# Single_Channel_fNIRS.net
KiCad netlist of a schematic drawn in Altium Designer
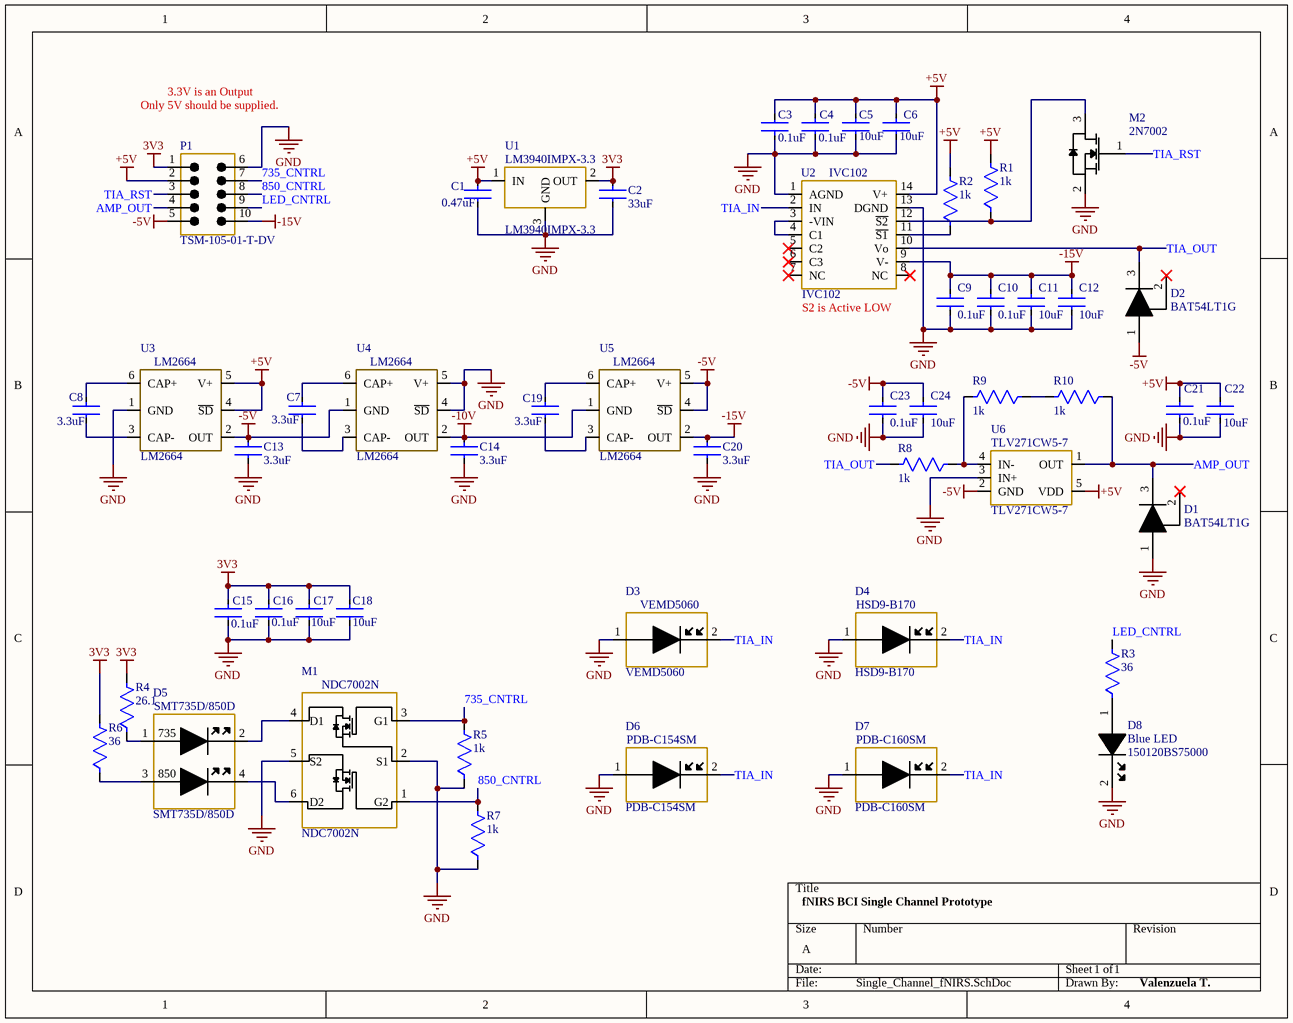
[diagram p0: Single_Channel_fNIRS.SchDoc]

(export (version "E")
  (design (tool "Eeschema 10.0.6"))
  (components
    (comp (ref "C1")
      (value "0.47uF")
      (footprint "CAPC3216X180N")
      (description "1206")
      (libsource (lib "Single_Channel_fNIRS") (part "C3216X7R2A474K160AA"))
    )
    (comp (ref "C2")
      (value "33uF")
      (footprint "CAPC3216X180N")
      (description "1206")
      (libsource (lib "Single_Channel_fNIRS") (part "C3216X5R1E336M160AC"))
    )
    (comp (ref "C3")
      (value "0.1uF")
      (footprint "CAPC3216X180N")
      (description "1206")
      (fields (field (name "TOLERANCE") "0.1") (field (name "MANUFACTURER") "KEMET"))
      (libsource (lib "Single_Channel_fNIRS") (part "C1206C104K5RAC7210"))
    )
    (comp (ref "C4")
      (value "0.1uF")
      (footprint "CAPC3216X180N")
      (description "1206")
      (fields (field (name "TOLERANCE") "0.1") (field (name "MANUFACTURER") "KEMET"))
      (libsource (lib "Single_Channel_fNIRS") (part "C1206C104K5RAC7210"))
    )
    (comp (ref "C5")
      (value "10uF")
      (footprint "CAPC3216X180N")
      (description "1206")
      (libsource (lib "Single_Channel_fNIRS") (part "CL31B106KOHNNWE"))
    )
    (comp (ref "C6")
      (value "10uF")
      (footprint "CAPC3216X180N")
      (description "1206")
      (libsource (lib "Single_Channel_fNIRS") (part "CL31B106KOHNNWE"))
    )
    (comp (ref "C7")
      (value "3.3uF")
      (footprint "CAPC1210(3225)190_M")
      (description "1210")
      (libsource (lib "Single_Channel_fNIRS") (part "C1210C335K5RAC7800"))
    )
    (comp (ref "C8")
      (value "3.3uF")
      (footprint "CAPC1210(3225)190_M")
      (description "1210")
      (libsource (lib "Single_Channel_fNIRS") (part "C1210C335K5RAC7800"))
    )
    (comp (ref "C9")
      (value "0.1uF")
      (footprint "CAPC3216X180N")
      (description "1206")
      (fields (field (name "TOLERANCE") "0.1") (field (name "MANUFACTURER") "KEMET"))
      (libsource (lib "Single_Channel_fNIRS") (part "C1206C104K5RAC7210"))
    )
    (comp (ref "C10")
      (value "0.1uF")
      (footprint "CAPC3216X180N")
      (description "1206")
      (fields (field (name "TOLERANCE") "0.1") (field (name "MANUFACTURER") "KEMET"))
      (libsource (lib "Single_Channel_fNIRS") (part "C1206C104K5RAC7210"))
    )
    (comp (ref "C11")
      (value "10uF")
      (footprint "CAPC3216X180N")
      (description "1206")
      (libsource (lib "Single_Channel_fNIRS") (part "CL31B106KOHNNWE"))
    )
    (comp (ref "C12")
      (value "10uF")
      (footprint "CAPC3216X180N")
      (description "1206")
      (libsource (lib "Single_Channel_fNIRS") (part "CL31B106KOHNNWE"))
    )
    (comp (ref "C13")
      (value "3.3uF")
      (footprint "CAPC1210(3225)190_M")
      (description "1210")
      (libsource (lib "Single_Channel_fNIRS") (part "C1210C335K5RAC7800"))
    )
    (comp (ref "C14")
      (value "3.3uF")
      (footprint "CAPC1210(3225)190_M")
      (description "1210")
      (libsource (lib "Single_Channel_fNIRS") (part "C1210C335K5RAC7800"))
    )
    (comp (ref "C15")
      (value "0.1uF")
      (footprint "CAPC3216X180N")
      (description "1206")
      (fields (field (name "TOLERANCE") "0.1") (field (name "MANUFACTURER") "KEMET"))
      (libsource (lib "Single_Channel_fNIRS") (part "C1206C104K5RAC7210"))
    )
    (comp (ref "C16")
      (value "0.1uF")
      (footprint "CAPC3216X180N")
      (description "1206")
      (fields (field (name "TOLERANCE") "0.1") (field (name "MANUFACTURER") "KEMET"))
      (libsource (lib "Single_Channel_fNIRS") (part "C1206C104K5RAC7210"))
    )
    (comp (ref "C17")
      (value "10uF")
      (footprint "CAPC3216X180N")
      (description "1206")
      (libsource (lib "Single_Channel_fNIRS") (part "CL31B106KOHNNWE"))
    )
    (comp (ref "C18")
      (value "10uF")
      (footprint "CAPC3216X180N")
      (description "1206")
      (libsource (lib "Single_Channel_fNIRS") (part "CL31B106KOHNNWE"))
    )
    (comp (ref "C19")
      (value "3.3uF")
      (footprint "CAPC1210(3225)190_M")
      (description "1210")
      (libsource (lib "Single_Channel_fNIRS") (part "C1210C335K5RAC7800"))
    )
    (comp (ref "C20")
      (value "3.3uF")
      (footprint "CAPC1210(3225)190_M")
      (description "1210")
      (libsource (lib "Single_Channel_fNIRS") (part "C1210C335K5RAC7800"))
    )
    (comp (ref "C21")
      (value "0.1uF")
      (footprint "CAPC3216X180N")
      (description "1206")
      (fields (field (name "TOLERANCE") "0.1") (field (name "MANUFACTURER") "KEMET"))
      (libsource (lib "Single_Channel_fNIRS") (part "C1206C104K5RAC7210"))
    )
    (comp (ref "C22")
      (value "10uF")
      (footprint "CAPC3216X180N")
      (description "1206")
      (libsource (lib "Single_Channel_fNIRS") (part "CL31B106KOHNNWE"))
    )
    (comp (ref "C23")
      (value "0.1uF")
      (footprint "CAPC3216X180N")
      (description "1206")
      (fields (field (name "TOLERANCE") "0.1") (field (name "MANUFACTURER") "KEMET"))
      (libsource (lib "Single_Channel_fNIRS") (part "C1206C104K5RAC7210"))
    )
    (comp (ref "C24")
      (value "10uF")
      (footprint "CAPC3216X180N")
      (description "1206")
      (libsource (lib "Single_Channel_fNIRS") (part "CL31B106KOHNNWE"))
    )
    (comp (ref "D1")
      (value "BAT54LT1G")
      (footprint "BAT54LT1")
      (description "Schottky Barrier Diode, 3-Pin SOT-23, Pb-Free, Tape and Reel")
      (fields (field (name "MANUFACTURER") "On Semiconductor"))
      (libsource (lib "Single_Channel_fNIRS") (part "BAT54L"))
    )
    (comp (ref "D2")
      (value "BAT54LT1G")
      (footprint "BAT54LT1")
      (description "Schottky Barrier Diode, 3-Pin SOT-23, Pb-Free, Tape and Reel")
      (fields (field (name "MANUFACTURER") "On Semiconductor"))
      (libsource (lib "Single_Channel_fNIRS") (part "BAT54L"))
    )
    (comp (ref "D3")
      (value "VEMD5060")
      (footprint "VEMD5060")
      (libsource (lib "Single_Channel_fNIRS") (part "VEMD5060"))
    )
    (comp (ref "D4")
      (value "HSD9-B170")
      (footprint "HSD9-B170")
      (libsource (lib "Single_Channel_fNIRS") (part "HSD9-B170"))
    )
    (comp (ref "D5")
      (value "SMT735D/850D")
      (footprint "SMT735D_850D")
      (libsource (lib "Single_Channel_fNIRS") (part "SMT735D/850D"))
    )
    (comp (ref "D6")
      (value "PDB-C154SM")
      (footprint "PDB-C154SM")
      (libsource (lib "Single_Channel_fNIRS") (part "PDB-C154SM"))
    )
    (comp (ref "D7")
      (value "PDB-C160SM")
      (footprint "DS-PDB-C160SM")
      (libsource (lib "Single_Channel_fNIRS") (part "PDB-C160SM"))
    )
    (comp (ref "D8")
      (value "Blue LED")
      (footprint "150120BS75000")
      (description "Single Color LED, Blue, Water Clear, 2mm")
      (fields
        (field (name "MANUFACTURER") "Wurth Electronics")
        (field (name "MANUFACTURER PART NUMBER") "150120BS75000")
        (field (name "SUPPLIER PART NUMBER 1") "150120BS75000")
      )
      (libsource (lib "Single_Channel_fNIRS") (part "150120BS75000"))
    )
    (comp (ref "M1")
      (value "NDC7002N")
      (footprint "FAIR-MA06A_V")
      (libsource (lib "Single_Channel_fNIRS") (part "NDC7002N"))
    )
    (comp (ref "M2")
      (value "2N7002")
      (footprint "STM-SOT-23-3_V")
      (description "N-channel 60 V, 1.8 Ohm, 0.35 A STripFET(TM) II Power MOSFET, SOT23")
      (fields (field (name "MANUFACTURER") "STMicroelectronics"))
      (libsource (lib "Single_Channel_fNIRS") (part "2N7002-TP"))
    )
    (comp (ref "P1")
      (value "TSM-105-01-T-DV")
      (footprint "SAMTEC_TSM-105-01-T-DV-TR")
      (fields (field (name "MANUFACTURER") "Samtec"))
      (libsource (lib "Single_Channel_fNIRS") (part "TSM-105-01-T-DV"))
    )
    (comp (ref "R1")
      (value "1k")
      (footprint "R1206")
      (description "1206 1kOhm")
      (libsource (lib "Single_Channel_fNIRS") (part "RT1206BRD071KL"))
    )
    (comp (ref "R2")
      (value "1k")
      (footprint "R1206")
      (description "1206 1kOhm")
      (libsource (lib "Single_Channel_fNIRS") (part "RT1206BRD071KL"))
    )
    (comp (ref "R3")
      (value "36")
      (footprint "R1206")
      (description "1206 36 Ohm")
      (fields
        (field (name "MANUFACTURER") "Yageo")
        (field (name "MANUFACTURER PART NUMBER") "RT1206BRD0736RL")
      )
      (libsource (lib "Single_Channel_fNIRS") (part "RT1206BRD0736RL"))
    )
    (comp (ref "R4")
      (value "26.1")
      (footprint "R1206")
      (description "1206 26.1 Ohm")
      (fields
        (field (name "OCTOPART") "https://octopart.com/rq73c2b26r1btd-te+connectivity-93911368")
        (field (name "MANUFACTURER PART NUMBER") "RQ73C2B26R1BTD")
      )
      (libsource (lib "Single_Channel_fNIRS") (part "RQ73C2B26R1BTD"))
    )
    (comp (ref "R5")
      (value "1k")
      (footprint "R1206")
      (description "1206 1kOhm")
      (libsource (lib "Single_Channel_fNIRS") (part "RT1206BRD071KL"))
    )
    (comp (ref "R6")
      (value "36")
      (footprint "R1206")
      (description "1206 36 Ohm")
      (fields
        (field (name "MANUFACTURER") "Yageo")
        (field (name "MANUFACTURER PART NUMBER") "RT1206BRD0736RL")
      )
      (libsource (lib "Single_Channel_fNIRS") (part "RT1206BRD0736RL"))
    )
    (comp (ref "R7")
      (value "1k")
      (footprint "R1206")
      (description "1206 1kOhm")
      (libsource (lib "Single_Channel_fNIRS") (part "RT1206BRD071KL"))
    )
    (comp (ref "R8")
      (value "1k")
      (footprint "R1206")
      (description "1206 1kOhm")
      (libsource (lib "Single_Channel_fNIRS") (part "RT1206BRD071KL"))
    )
    (comp (ref "R9")
      (value "1k")
      (footprint "R1206")
      (description "1206 1kOhm")
      (libsource (lib "Single_Channel_fNIRS") (part "RT1206BRD071KL"))
    )
    (comp (ref "R10")
      (value "1k")
      (footprint "R1206")
      (description "1206 1kOhm")
      (libsource (lib "Single_Channel_fNIRS") (part "RT1206BRD071KL"))
    )
    (comp (ref "U1")
      (value "LM3940IMPX-3.3")
      (footprint "LM3940")
      (libsource (lib "Single_Channel_fNIRS") (part "LM3940IMPX-3.3"))
    )
    (comp (ref "U2")
      (value "IVC102")
      (footprint "D0014A_M")
      (libsource (lib "Single_Channel_fNIRS") (part "IVC102"))
    )
    (comp (ref "U3")
      (value "LM2664")
      (footprint "LM2664")
      (description "Switched Capacitor Voltage Converter, 6-pin SOT-23")
      (fields (field (name "MANUFACTURER") "Texas Instruments"))
      (libsource (lib "Single_Channel_fNIRS") (part "LM2664"))
    )
    (comp (ref "U4")
      (value "LM2664")
      (footprint "LM2664")
      (description "Switched Capacitor Voltage Converter, 6-pin SOT-23")
      (fields (field (name "MANUFACTURER") "Texas Instruments"))
      (libsource (lib "Single_Channel_fNIRS") (part "LM2664"))
    )
    (comp (ref "U5")
      (value "LM2664")
      (footprint "LM2664")
      (description "Switched Capacitor Voltage Converter, 6-pin SOT-23")
      (fields (field (name "MANUFACTURER") "Texas Instruments"))
      (libsource (lib "Single_Channel_fNIRS") (part "LM2664"))
    )
    (comp (ref "U6")
      (value "TLV271CW5-7")
      (footprint "SOT95P285X145-5N")
      (libsource (lib "Single_Channel_fNIRS") (part "TLV271CW5-7"))
    )
  )
  (nets
    (net (code "1") (name "+5V") (class "Default")
      (node (ref "C1") (pin "1") (pinfunction "1_1") (pintype "passive"))
      (node (ref "C21") (pin "1") (pinfunction "1_1") (pintype "passive"))
      (node (ref "C22") (pin "1") (pinfunction "1_1") (pintype "passive"))
      (node (ref "C3") (pin "2") (pinfunction "2_2") (pintype "passive"))
      (node (ref "C4") (pin "1") (pinfunction "1_1") (pintype "passive"))
      (node (ref "C5") (pin "1") (pinfunction "1_1") (pintype "passive"))
      (node (ref "C6") (pin "1") (pinfunction "1_1") (pintype "passive"))
      (node (ref "P1") (pin "2") (pinfunction "2_2") (pintype "passive"))
      (node (ref "R1") (pin "2") (pinfunction "2_2") (pintype "passive"))
      (node (ref "R2") (pin "2") (pinfunction "2_2") (pintype "passive"))
      (node (ref "U1") (pin "1") (pinfunction "IN_1") (pintype "passive"))
      (node (ref "U2") (pin "14") (pinfunction "V+_14") (pintype "passive"))
      (node (ref "U3") (pin "4") (pinfunction "~{SD}_4") (pintype "passive"))
      (node (ref "U3") (pin "5") (pinfunction "V+_5") (pintype "passive"))
      (node (ref "U6") (pin "5") (pinfunction "VDD_5") (pintype "passive"))
    )
    (net (code "2") (name "-5V") (class "Default")
      (node (ref "C13") (pin "1") (pinfunction "1_1") (pintype "passive"))
      (node (ref "C23") (pin "1") (pinfunction "1_1") (pintype "passive"))
      (node (ref "C24") (pin "1") (pinfunction "1_1") (pintype "passive"))
      (node (ref "D2") (pin "1") (pinfunction "A_1") (pintype "passive"))
      (node (ref "P1") (pin "5") (pinfunction "5_5") (pintype "passive"))
      (node (ref "U3") (pin "2") (pinfunction "OUT_2") (pintype "passive"))
      (node (ref "U4") (pin "1") (pinfunction "GND_1") (pintype "passive"))
      (node (ref "U5") (pin "4") (pinfunction "~{SD}_4") (pintype "passive"))
      (node (ref "U5") (pin "5") (pinfunction "V+_5") (pintype "passive"))
      (node (ref "U6") (pin "2") (pinfunction "GND_2") (pintype "passive"))
    )
    (net (code "3") (name "-10V") (class "Default")
      (node (ref "C14") (pin "1") (pinfunction "1_1") (pintype "passive"))
      (node (ref "U4") (pin "2") (pinfunction "OUT_2") (pintype "passive"))
      (node (ref "U5") (pin "1") (pinfunction "GND_1") (pintype "passive"))
    )
    (net (code "4") (name "-15V") (class "Default")
      (node (ref "C10") (pin "1") (pinfunction "1_1") (pintype "passive"))
      (node (ref "C11") (pin "1") (pinfunction "1_1") (pintype "passive"))
      (node (ref "C12") (pin "1") (pinfunction "1_1") (pintype "passive"))
      (node (ref "C20") (pin "1") (pinfunction "1_1") (pintype "passive"))
      (node (ref "C9") (pin "1") (pinfunction "1_1") (pintype "passive"))
      (node (ref "P1") (pin "10") (pinfunction "10_10") (pintype "passive"))
      (node (ref "U2") (pin "9") (pinfunction "V-_9") (pintype "passive"))
      (node (ref "U5") (pin "2") (pinfunction "OUT_2") (pintype "passive"))
    )
    (net (code "5") (name "/735_CNTRL") (class "Default")
      (node (ref "M1") (pin "3") (pinfunction "G1_3") (pintype "passive"))
      (node (ref "P1") (pin "7") (pinfunction "7_7") (pintype "passive"))
      (node (ref "R5") (pin "2") (pinfunction "2_2") (pintype "passive"))
    )
    (net (code "6") (name "/850_CNTRL") (class "Default")
      (node (ref "M1") (pin "1") (pinfunction "G2_1") (pintype "passive"))
      (node (ref "P1") (pin "8") (pinfunction "8_8") (pintype "passive"))
      (node (ref "R7") (pin "2") (pinfunction "2_2") (pintype "passive"))
    )
    (net (code "7") (name "/AMP_OUT") (class "Default")
      (node (ref "D1") (pin "3") (pinfunction "K_3") (pintype "passive"))
      (node (ref "P1") (pin "4") (pinfunction "4_4") (pintype "passive"))
      (node (ref "R10") (pin "1") (pinfunction "1_1") (pintype "passive"))
      (node (ref "U6") (pin "1") (pinfunction "OUT_1") (pintype "passive"))
    )
    (net (code "8") (name "/LED_CNTRL") (class "Default")
      (node (ref "P1") (pin "9") (pinfunction "9_9") (pintype "passive"))
      (node (ref "R3") (pin "2") (pinfunction "2_2") (pintype "passive"))
    )
    (net (code "9") (name "/TIA_IN") (class "Default")
      (node (ref "D3") (pin "2") (pinfunction "2_2") (pintype "passive"))
      (node (ref "D4") (pin "2") (pinfunction "2_2") (pintype "passive"))
      (node (ref "D6") (pin "2") (pinfunction "2_2") (pintype "passive"))
      (node (ref "D7") (pin "2") (pinfunction "2_2") (pintype "passive"))
      (node (ref "U2") (pin "2") (pinfunction "IN_2") (pintype "passive"))
    )
    (net (code "10") (name "/TIA_OUT") (class "Default")
      (node (ref "D2") (pin "3") (pinfunction "K_3") (pintype "passive"))
      (node (ref "R8") (pin "2") (pinfunction "2_2") (pintype "passive"))
      (node (ref "U2") (pin "10") (pinfunction "Vo_10") (pintype "passive"))
    )
    (net (code "11") (name "/TIA_RST") (class "Default")
      (node (ref "M2") (pin "1") (pinfunction "G_1") (pintype "passive"))
      (node (ref "P1") (pin "3") (pinfunction "3_3") (pintype "passive"))
    )
    (net (code "12") (name "3V3") (class "Default")
      (node (ref "C15") (pin "1") (pinfunction "1_1") (pintype "passive"))
      (node (ref "C16") (pin "1") (pinfunction "1_1") (pintype "passive"))
      (node (ref "C17") (pin "1") (pinfunction "1_1") (pintype "passive"))
      (node (ref "C18") (pin "1") (pinfunction "1_1") (pintype "passive"))
      (node (ref "C2") (pin "1") (pinfunction "1_1") (pintype "passive"))
      (node (ref "P1") (pin "1") (pinfunction "1_1") (pintype "passive"))
      (node (ref "R4") (pin "2") (pinfunction "2_2") (pintype "passive"))
      (node (ref "R6") (pin "2") (pinfunction "2_2") (pintype "passive"))
      (node (ref "U1") (pin "2") (pinfunction "OUT_2") (pintype "passive"))
    )
    (net (code "13") (name "GND") (class "Default")
      (node (ref "C1") (pin "2") (pinfunction "2_2") (pintype "passive"))
      (node (ref "C10") (pin "2") (pinfunction "2_2") (pintype "passive"))
      (node (ref "C11") (pin "2") (pinfunction "2_2") (pintype "passive"))
      (node (ref "C12") (pin "2") (pinfunction "2_2") (pintype "passive"))
      (node (ref "C13") (pin "2") (pinfunction "2_2") (pintype "passive"))
      (node (ref "C14") (pin "2") (pinfunction "2_2") (pintype "passive"))
      (node (ref "C15") (pin "2") (pinfunction "2_2") (pintype "passive"))
      (node (ref "C16") (pin "2") (pinfunction "2_2") (pintype "passive"))
      (node (ref "C17") (pin "2") (pinfunction "2_2") (pintype "passive"))
      (node (ref "C18") (pin "2") (pinfunction "2_2") (pintype "passive"))
      (node (ref "C2") (pin "2") (pinfunction "2_2") (pintype "passive"))
      (node (ref "C20") (pin "2") (pinfunction "2_2") (pintype "passive"))
      (node (ref "C21") (pin "2") (pinfunction "2_2") (pintype "passive"))
      (node (ref "C22") (pin "2") (pinfunction "2_2") (pintype "passive"))
      (node (ref "C23") (pin "2") (pinfunction "2_2") (pintype "passive"))
      (node (ref "C24") (pin "2") (pinfunction "2_2") (pintype "passive"))
      (node (ref "C3") (pin "1") (pinfunction "1_1") (pintype "passive"))
      (node (ref "C4") (pin "2") (pinfunction "2_2") (pintype "passive"))
      (node (ref "C5") (pin "2") (pinfunction "2_2") (pintype "passive"))
      (node (ref "C6") (pin "2") (pinfunction "2_2") (pintype "passive"))
      (node (ref "C9") (pin "2") (pinfunction "2_2") (pintype "passive"))
      (node (ref "D1") (pin "1") (pinfunction "A_1") (pintype "passive"))
      (node (ref "D3") (pin "1") (pinfunction "1_1") (pintype "passive"))
      (node (ref "D4") (pin "1") (pinfunction "1_1") (pintype "passive"))
      (node (ref "D6") (pin "1") (pinfunction "1_1") (pintype "passive"))
      (node (ref "D7") (pin "1") (pinfunction "1_1") (pintype "passive"))
      (node (ref "D8") (pin "2") (pinfunction "2_2") (pintype "passive"))
      (node (ref "M1") (pin "2") (pinfunction "S1_2") (pintype "passive"))
      (node (ref "M1") (pin "5") (pinfunction "S2_5") (pintype "passive"))
      (node (ref "M2") (pin "2") (pinfunction "S_2") (pintype "passive"))
      (node (ref "P1") (pin "6") (pinfunction "6_6") (pintype "passive"))
      (node (ref "R5") (pin "1") (pinfunction "1_1") (pintype "passive"))
      (node (ref "R7") (pin "1") (pinfunction "1_1") (pintype "passive"))
      (node (ref "U1") (pin "3") (pinfunction "GND_3") (pintype "passive"))
      (node (ref "U2") (pin "1") (pinfunction "AGND_1") (pintype "passive"))
      (node (ref "U2") (pin "13") (pinfunction "DGND_13") (pintype "passive"))
      (node (ref "U3") (pin "1") (pinfunction "GND_1") (pintype "passive"))
      (node (ref "U4") (pin "4") (pinfunction "~{SD}_4") (pintype "passive"))
      (node (ref "U4") (pin "5") (pinfunction "V+_5") (pintype "passive"))
      (node (ref "U6") (pin "3") (pinfunction "IN+_3") (pintype "passive"))
    )
    (net (code "14") (name "Net-(D5-Pad1)") (class "Default")
      (node (ref "D5") (pin "1") (pinfunction "1_1") (pintype "passive"))
      (node (ref "R4") (pin "1") (pinfunction "1_1") (pintype "passive"))
    )
    (net (code "15") (name "Net-(D5-Pad3)") (class "Default")
      (node (ref "D5") (pin "3") (pinfunction "3_3") (pintype "passive"))
      (node (ref "R6") (pin "1") (pinfunction "1_1") (pintype "passive"))
    )
    (net (code "16") (name "Net-(D8-Pad1)") (class "Default")
      (node (ref "D8") (pin "1") (pinfunction "1_1") (pintype "passive"))
      (node (ref "R3") (pin "1") (pinfunction "1_1") (pintype "passive"))
    )
    (net (code "17") (name "Net-(M1-D1)") (class "Default")
      (node (ref "D5") (pin "2") (pinfunction "2_2") (pintype "passive"))
      (node (ref "M1") (pin "4") (pinfunction "D1_4") (pintype "passive"))
    )
    (net (code "18") (name "Net-(M1-D2)") (class "Default")
      (node (ref "D5") (pin "4") (pinfunction "4_4") (pintype "passive"))
      (node (ref "M1") (pin "6") (pinfunction "D2_6") (pintype "passive"))
    )
    (net (code "19") (name "Net-(M2-D)") (class "Default")
      (node (ref "M2") (pin "3") (pinfunction "D_3") (pintype "passive"))
      (node (ref "R1") (pin "1") (pinfunction "1_1") (pintype "passive"))
      (node (ref "U2") (pin "12") (pinfunction "~{S2}_12") (pintype "passive"))
    )
    (net (code "20") (name "Net-(R10-Pad2)") (class "Default")
      (node (ref "R10") (pin "2") (pinfunction "2_2") (pintype "passive"))
      (node (ref "R9") (pin "1") (pinfunction "1_1") (pintype "passive"))
    )
    (net (code "21") (name "Net-(U2--VIN)") (class "Default")
      (node (ref "U2") (pin "3") (pinfunction "-VIN_3") (pintype "passive"))
      (node (ref "U2") (pin "4") (pinfunction "C1_4") (pintype "passive"))
    )
    (net (code "22") (name "Net-(U2-~{S1})") (class "Default")
      (node (ref "R2") (pin "1") (pinfunction "1_1") (pintype "passive"))
      (node (ref "U2") (pin "11") (pinfunction "~{S1}_11") (pintype "passive"))
    )
    (net (code "23") (name "Net-(U3-CAP+)") (class "Default")
      (node (ref "C8") (pin "1") (pinfunction "1_1") (pintype "passive"))
      (node (ref "U3") (pin "6") (pinfunction "CAP+_6") (pintype "passive"))
    )
    (net (code "24") (name "Net-(U3-CAP-)") (class "Default")
      (node (ref "C8") (pin "2") (pinfunction "2_2") (pintype "passive"))
      (node (ref "U3") (pin "3") (pinfunction "CAP-_3") (pintype "passive"))
    )
    (net (code "25") (name "Net-(U4-CAP+)") (class "Default")
      (node (ref "C7") (pin "1") (pinfunction "1_1") (pintype "passive"))
      (node (ref "U4") (pin "6") (pinfunction "CAP+_6") (pintype "passive"))
    )
    (net (code "26") (name "Net-(U4-CAP-)") (class "Default")
      (node (ref "C7") (pin "2") (pinfunction "2_2") (pintype "passive"))
      (node (ref "U4") (pin "3") (pinfunction "CAP-_3") (pintype "passive"))
    )
    (net (code "27") (name "Net-(U5-CAP+)") (class "Default")
      (node (ref "C19") (pin "1") (pinfunction "1_1") (pintype "passive"))
      (node (ref "U5") (pin "6") (pinfunction "CAP+_6") (pintype "passive"))
    )
    (net (code "28") (name "Net-(U5-CAP-)") (class "Default")
      (node (ref "C19") (pin "2") (pinfunction "2_2") (pintype "passive"))
      (node (ref "U5") (pin "3") (pinfunction "CAP-_3") (pintype "passive"))
    )
    (net (code "29") (name "Net-(U6-IN-)") (class "Default")
      (node (ref "R8") (pin "1") (pinfunction "1_1") (pintype "passive"))
      (node (ref "R9") (pin "2") (pinfunction "2_2") (pintype "passive"))
      (node (ref "U6") (pin "4") (pinfunction "IN-_4") (pintype "passive"))
    )
    (net (code "30") (name "unconnected-(D1-NC-Pad2)") (class "Default")
      (node (ref "D1") (pin "2") (pinfunction "NC_2") (pintype "passive+no_connect"))
    )
    (net (code "31") (name "unconnected-(D2-NC-Pad2)") (class "Default")
      (node (ref "D2") (pin "2") (pinfunction "NC_2") (pintype "passive+no_connect"))
    )
    (net (code "32") (name "unconnected-(U2-C2-Pad5)") (class "Default")
      (node (ref "U2") (pin "5") (pinfunction "C2_5") (pintype "passive+no_connect"))
    )
    (net (code "33") (name "unconnected-(U2-C3-Pad6)") (class "Default")
      (node (ref "U2") (pin "6") (pinfunction "C3_6") (pintype "passive+no_connect"))
    )
    (net (code "34") (name "unconnected-(U2-NC-Pad7)") (class "Default")
      (node (ref "U2") (pin "7") (pinfunction "NC_7") (pintype "passive+no_connect"))
    )
    (net (code "35") (name "unconnected-(U2-NC-Pad8)") (class "Default")
      (node (ref "U2") (pin "8") (pinfunction "NC_8") (pintype "passive+no_connect"))
    )
  )
)
